# Nguyen_Ly.net
KiCad netlist of a schematic drawn in Altium Designer
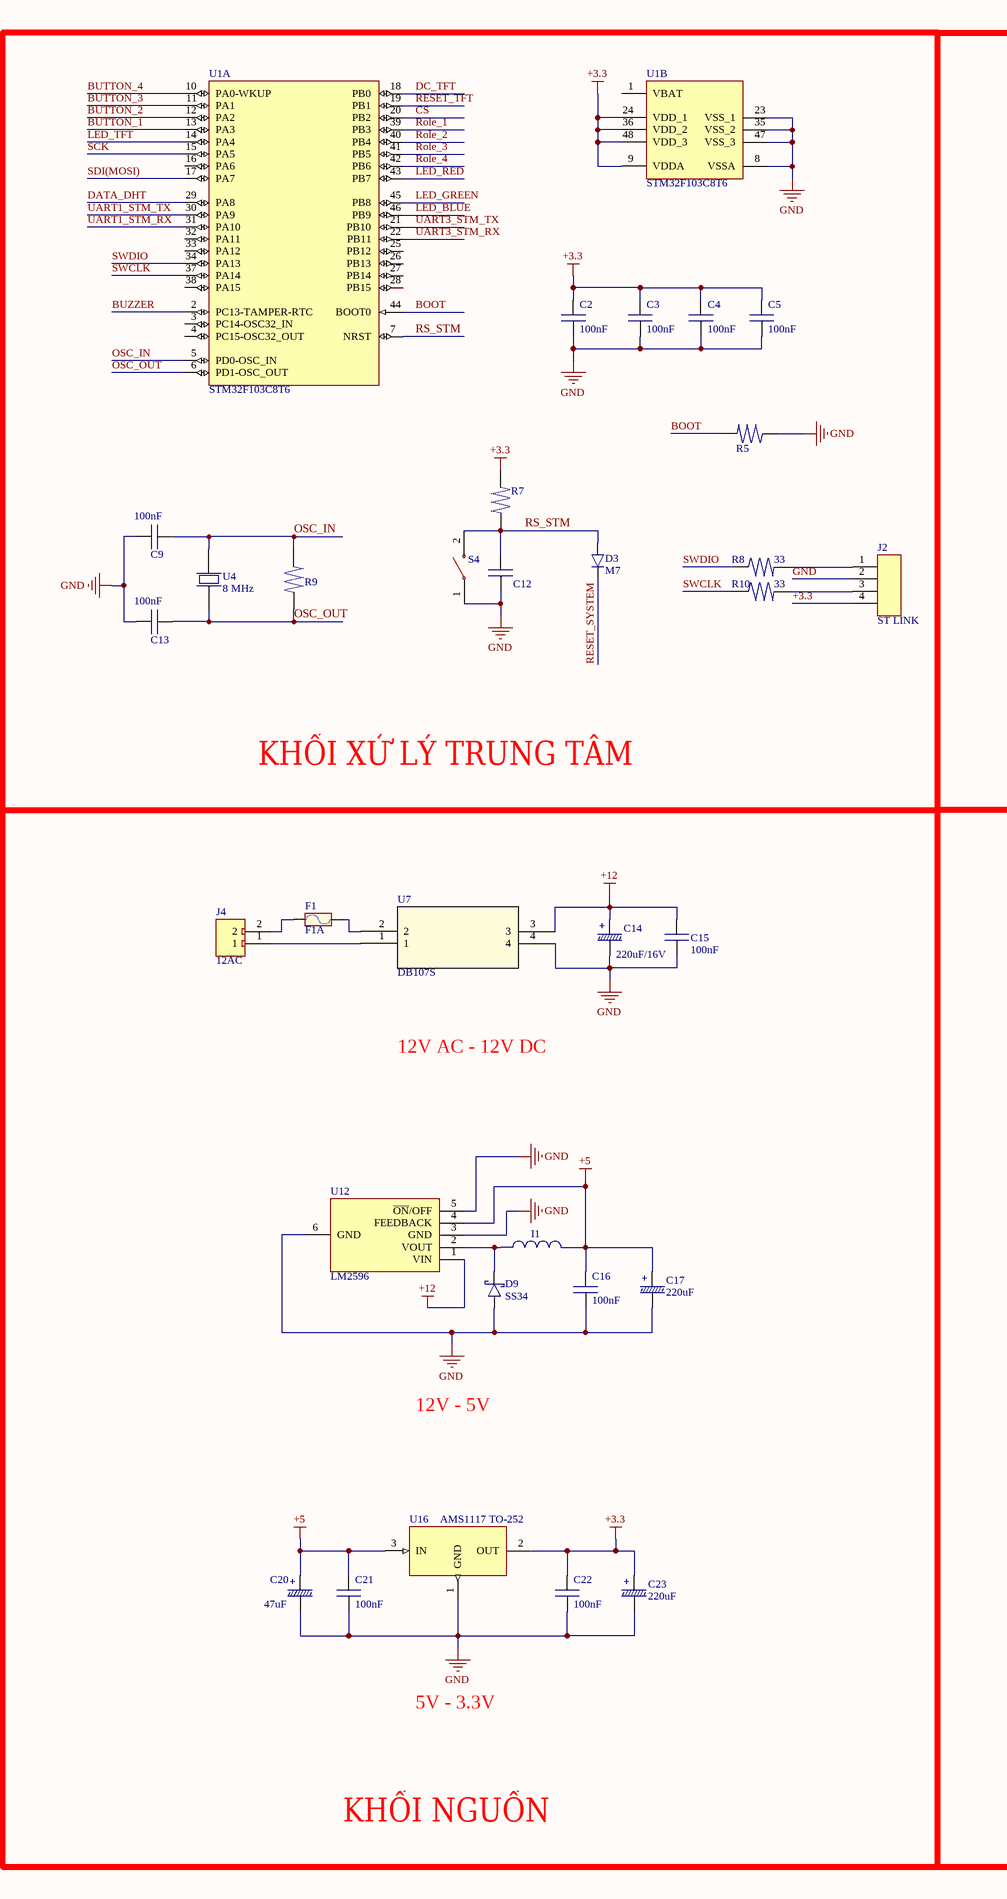
[diagram p0: Nguyen_Ly.SchDoc, left]
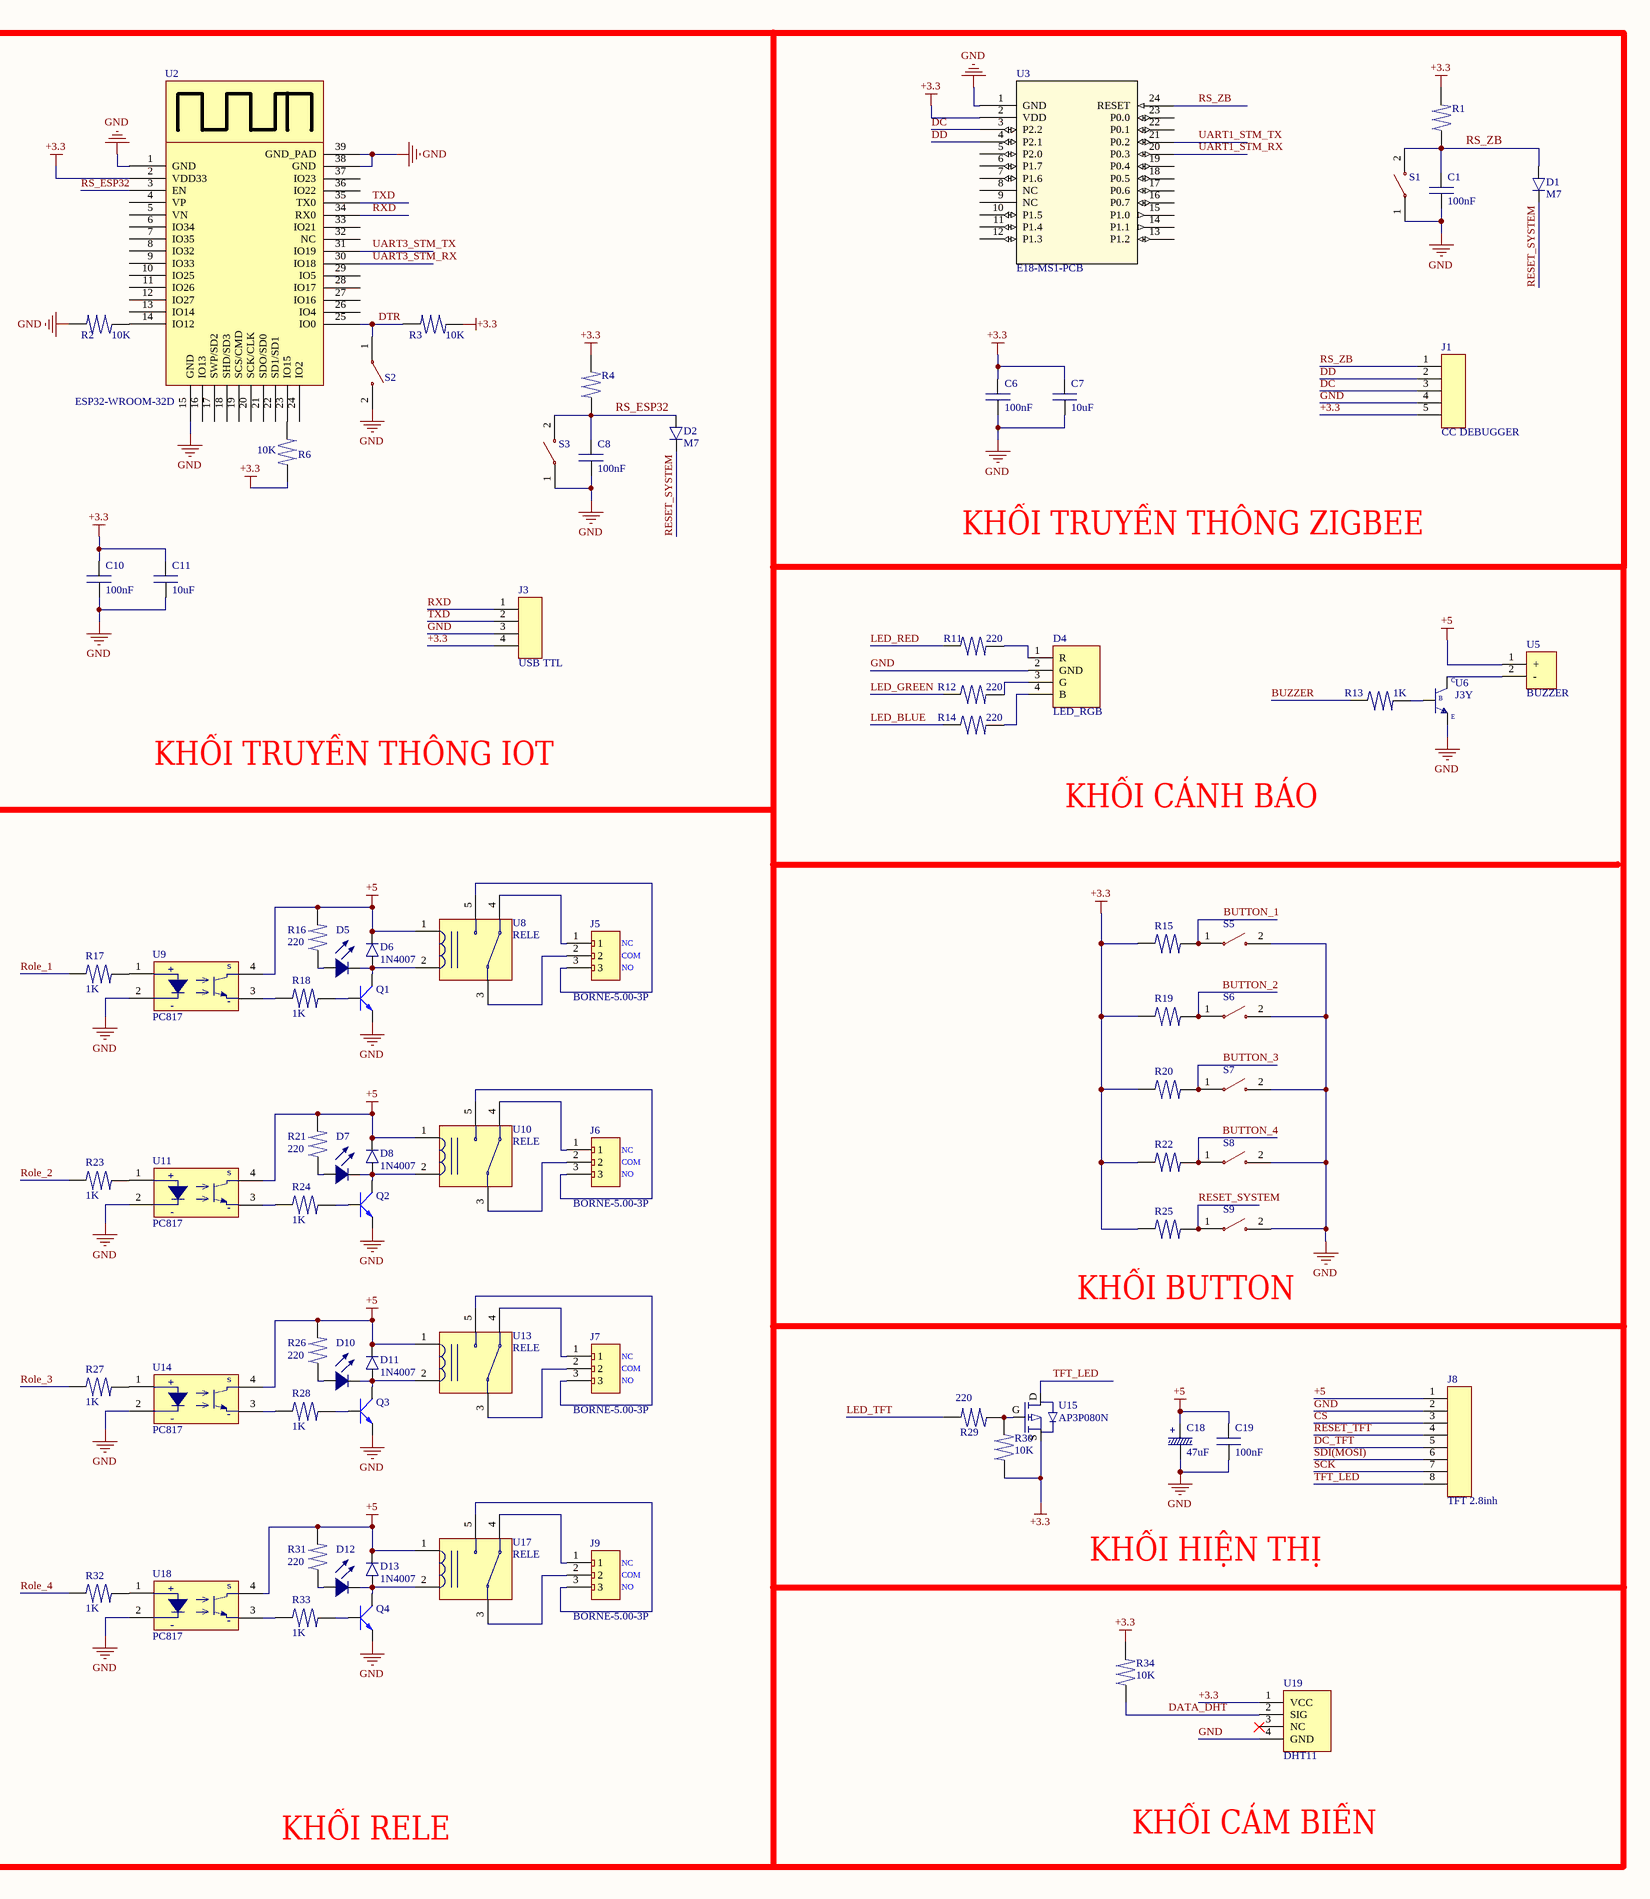
[diagram p1: Nguyen_Ly.SchDoc, right]

(export (version "E")
  (design (tool "Eeschema 10.0.6"))
  (components
    (comp (ref "C1")
      (value "100nF")
      (footprint "CAPACITOR 0805")
      (description "Generic Capacitor 0805, 2x1.25x1.4mm.")
      (libsource (lib "MyComponents") (part "CAPACITOR 0805"))
    )
    (comp (ref "C2")
      (value "100nF")
      (footprint "CAPACITOR 0805")
      (description "Generic Capacitor 0805, 2x1.25x1.4mm.")
      (libsource (lib "MyComponents") (part "CAPACITOR 0805"))
    )
    (comp (ref "C3")
      (value "100nF")
      (footprint "CAPACITOR 0805")
      (description "Generic Capacitor 0805, 2x1.25x1.4mm.")
      (libsource (lib "MyComponents") (part "CAPACITOR 0805"))
    )
    (comp (ref "C4")
      (value "100nF")
      (footprint "CAPACITOR 0805")
      (description "Generic Capacitor 0805, 2x1.25x1.4mm.")
      (libsource (lib "MyComponents") (part "CAPACITOR 0805"))
    )
    (comp (ref "C5")
      (value "100nF")
      (footprint "CAPACITOR 0805")
      (description "Generic Capacitor 0805, 2x1.25x1.4mm.")
      (libsource (lib "MyComponents") (part "CAPACITOR 0805"))
    )
    (comp (ref "C6")
      (value "100nF")
      (footprint "CAPACITOR 0805")
      (description "Generic Capacitor 0805, 2x1.25x1.4mm.")
      (libsource (lib "MyComponents") (part "CAPACITOR 0805"))
    )
    (comp (ref "C7")
      (value "10uF")
      (footprint "CAPACITOR 0805")
      (description "Generic Capacitor 0805, 2x1.25x1.4mm.")
      (libsource (lib "MyComponents") (part "CAPACITOR 0805"))
    )
    (comp (ref "C8")
      (value "100nF")
      (footprint "CAPACITOR 0805")
      (description "Generic Capacitor 0805, 2x1.25x1.4mm.")
      (libsource (lib "MyComponents") (part "CAPACITOR 0805"))
    )
    (comp (ref "C9")
      (value "100nF")
      (footprint "CAPACITOR 0805")
      (description "Generic Capacitor 0805, 2x1.25x1.4mm.")
      (libsource (lib "MyComponents") (part "CAPACITOR 0805"))
    )
    (comp (ref "C10")
      (value "100nF")
      (footprint "CAPACITOR 0805")
      (description "Generic Capacitor 0805, 2x1.25x1.4mm.")
      (libsource (lib "MyComponents") (part "CAPACITOR 0805"))
    )
    (comp (ref "C11")
      (value "10uF")
      (footprint "CAPACITOR 0805")
      (description "Generic Capacitor 0805, 2x1.25x1.4mm.")
      (libsource (lib "MyComponents") (part "CAPACITOR 0805"))
    )
    (comp (ref "C12")
      (value "CAPACITOR 0805")
      (footprint "CAPACITOR 0805")
      (description "Generic Capacitor 0805, 2x1.25x1.4mm.")
      (libsource (lib "MyComponents") (part "CAPACITOR 0805"))
    )
    (comp (ref "C13")
      (value "100nF")
      (footprint "CAPACITOR 0805")
      (description "Generic Capacitor 0805, 2x1.25x1.4mm.")
      (libsource (lib "MyComponents") (part "CAPACITOR 0805"))
    )
    (comp (ref "C14")
      (value "220uF/16V")
      (footprint "ALUMINUM_7mm")
      (description "Aluminum Capacitor 220uF/16V 7mm")
      (libsource (lib "MyComponents") (part "220uF/16V"))
    )
    (comp (ref "C15")
      (value "100nF")
      (footprint "CAPACITOR 0805")
      (description "Generic Capacitor 0805, 2x1.25x1.4mm.")
      (libsource (lib "MyComponents") (part "CAPACITOR 0805"))
    )
    (comp (ref "C16")
      (value "100nF")
      (footprint "CAPACITOR 0805")
      (description "Generic Capacitor 0805, 2x1.25x1.4mm.")
      (libsource (lib "MyComponents") (part "CAPACITOR 0805"))
    )
    (comp (ref "C17")
      (value "220uF")
      (footprint "ALUMINUM_7mm")
      (description "Aluminum Capacitor 220uF/16V 7mm")
      (libsource (lib "MyComponents") (part "220uF/16V"))
    )
    (comp (ref "C18")
      (value "47uF")
      (footprint "ALUMINUM_5mm")
      (description "Aluminum Capacitor 47uF/16V 5mm")
      (libsource (lib "MyComponents") (part "47uF/16V"))
    )
    (comp (ref "C19")
      (value "100nF")
      (footprint "CAPACITOR 0805")
      (description "Generic Capacitor 0805, 2x1.25x1.4mm.")
      (libsource (lib "MyComponents") (part "CAPACITOR 0805"))
    )
    (comp (ref "C20")
      (value "47uF")
      (footprint "ALUMINUM_5mm")
      (description "Aluminum Capacitor 47uF/16V 5mm")
      (libsource (lib "MyComponents") (part "47uF/16V"))
    )
    (comp (ref "C21")
      (value "100nF")
      (footprint "CAPACITOR 0805")
      (description "Generic Capacitor 0805, 2x1.25x1.4mm.")
      (libsource (lib "MyComponents") (part "CAPACITOR 0805"))
    )
    (comp (ref "C22")
      (value "100nF")
      (footprint "CAPACITOR 0805")
      (description "Generic Capacitor 0805, 2x1.25x1.4mm.")
      (libsource (lib "MyComponents") (part "CAPACITOR 0805"))
    )
    (comp (ref "C23")
      (value "220uF")
      (footprint "ALUMINUM_7mm")
      (description "Aluminum Capacitor 220uF/16V 7mm")
      (libsource (lib "MyComponents") (part "220uF/16V"))
    )
    (comp (ref "D1")
      (value "M7")
      (footprint "DIODE_SMA")
      (description "Rectifiers Diode 1000V 1A SMA")
      (libsource (lib "MyComponents") (part "M7"))
    )
    (comp (ref "D2")
      (value "M7")
      (footprint "DIODE_SMA")
      (description "Rectifiers Diode 1000V 1A SMA")
      (libsource (lib "MyComponents") (part "M7"))
    )
    (comp (ref "D3")
      (value "M7")
      (footprint "DIODE_SMA")
      (description "Rectifiers Diode 1000V 1A SMA")
      (libsource (lib "MyComponents") (part "M7"))
    )
    (comp (ref "D4")
      (value "LED_RGB")
      (footprint "LED_RGB_5mm")
      (description "LED RGB 4 Pins 5mm Common Cathode.")
      (libsource (lib "MyComponents") (part "LED_RGB_5mm"))
    )
    (comp (ref "D5")
      (value "LED_5mm_RED")
      (footprint "LED_5mm_RED")
      (description "LED PTH 5mm Red.")
      (libsource (lib "MyComponents") (part "LED_5mm_RED"))
    )
    (comp (ref "D6")
      (value "1N4007")
      (footprint "1N4007")
      (description "Rectifier Diode 1000V 1A DO-41")
      (libsource (lib "MyComponents") (part "1N4007"))
    )
    (comp (ref "D7")
      (value "LED_5mm_RED")
      (footprint "LED_5mm_RED")
      (description "LED PTH 5mm Red.")
      (libsource (lib "MyComponents") (part "LED_5mm_RED"))
    )
    (comp (ref "D8")
      (value "1N4007")
      (footprint "1N4007")
      (description "Rectifier Diode 1000V 1A DO-41")
      (libsource (lib "MyComponents") (part "1N4007"))
    )
    (comp (ref "D9")
      (value "SS34")
      (footprint "DIODE_SMA")
      (description "Rectifier Schottky 40V 3A SMA")
      (libsource (lib "MyComponents") (part "SS34"))
    )
    (comp (ref "D10")
      (value "LED_5mm_RED")
      (footprint "LED_5mm_RED")
      (description "LED PTH 5mm Red.")
      (libsource (lib "MyComponents") (part "LED_5mm_RED"))
    )
    (comp (ref "D11")
      (value "1N4007")
      (footprint "1N4007")
      (description "Rectifier Diode 1000V 1A DO-41")
      (libsource (lib "MyComponents") (part "1N4007"))
    )
    (comp (ref "D12")
      (value "LED_5mm_RED")
      (footprint "LED_5mm_RED")
      (description "LED PTH 5mm Red.")
      (libsource (lib "MyComponents") (part "LED_5mm_RED"))
    )
    (comp (ref "D13")
      (value "1N4007")
      (footprint "1N4007")
      (description "Rectifier Diode 1000V 1A DO-41")
      (libsource (lib "MyComponents") (part "1N4007"))
    )
    (comp (ref "F1")
      (value "F1A")
      (footprint "Fuse")
      (description "Fuse")
      (fields (field (name "DESIGNED BY") "VanDungEvn"))
      (libsource (lib "Thuvien3D") (part "Fuse"))
    )
    (comp (ref "I1")
      (value "1260")
      (footprint "1260")
      (description "Generic Encapsulated Inductor 1260.")
      (libsource (lib "MyComponents") (part "1260"))
    )
    (comp (ref "J1")
      (value "CC DEBUGGER")
      (footprint "MALE-2.54-5P")
      (description "Male Header Connector 2.54mm 5 Pins.")
      (libsource (lib "MyComponents") (part "MALE-2.54-5P"))
    )
    (comp (ref "J2")
      (value "ST LINK")
      (footprint "MALE-2.54-4P")
      (description "Male Header Connector 2.54mm 4 Pins.")
      (libsource (lib "MyComponents") (part "MALE-2.54-4P"))
    )
    (comp (ref "J3")
      (value "USB TTL")
      (footprint "MALE-2.54-4P")
      (description "Male Header Connector 2.54mm 4 Pins.")
      (libsource (lib "MyComponents") (part "MALE-2.54-4P"))
    )
    (comp (ref "J4")
      (value "12AC")
      (footprint "BORNE-5.00-2P")
      (description "Borne 2 Vias, Pitch 5mm.")
      (libsource (lib "MyComponents") (part "BORNE-5.00-2P"))
    )
    (comp (ref "J5")
      (value "BORNE-5.00-3P")
      (footprint "BORNE-5.00-3P")
      (description "Borne 3 Vias, Pitch 5mm.")
      (libsource (lib "MyComponents") (part "BORNE-5.00-3P"))
    )
    (comp (ref "J6")
      (value "BORNE-5.00-3P")
      (footprint "BORNE-5.00-3P")
      (description "Borne 3 Vias, Pitch 5mm.")
      (libsource (lib "MyComponents") (part "BORNE-5.00-3P"))
    )
    (comp (ref "J7")
      (value "BORNE-5.00-3P")
      (footprint "BORNE-5.00-3P")
      (description "Borne 3 Vias, Pitch 5mm.")
      (libsource (lib "MyComponents") (part "BORNE-5.00-3P"))
    )
    (comp (ref "J8")
      (value "TFT 2.8inh")
      (footprint "MALE-2.54-8P")
      (description "Male Header Connector 2.54mm 8 Pins.")
      (libsource (lib "MyComponents") (part "MALE-2.54-8P"))
    )
    (comp (ref "J9")
      (value "BORNE-5.00-3P")
      (footprint "BORNE-5.00-3P")
      (description "Borne 3 Vias, Pitch 5mm.")
      (libsource (lib "MyComponents") (part "BORNE-5.00-3P"))
    )
    (comp (ref "Q1")
      (value "C9014")
      (footprint "QTO-92")
      (description "P 600mW, EBC")
      (libsource (lib "Thuvien3D") (part "NPN_EBC"))
    )
    (comp (ref "Q2")
      (value "C9014")
      (footprint "QTO-92")
      (description "P 600mW, EBC")
      (libsource (lib "Thuvien3D") (part "NPN_EBC"))
    )
    (comp (ref "Q3")
      (value "C9014")
      (footprint "QTO-92")
      (description "P 600mW, EBC")
      (libsource (lib "Thuvien3D") (part "NPN_EBC"))
    )
    (comp (ref "Q4")
      (value "C9014")
      (footprint "QTO-92")
      (description "P 600mW, EBC")
      (libsource (lib "Thuvien3D") (part "NPN_EBC"))
    )
    (comp (ref "R1")
      (value "RESISTOR_0805")
      (footprint "RESISTOR_0805")
      (description "Generic Resistor 0805.")
      (libsource (lib "MyComponents") (part "RESISTOR_0805"))
    )
    (comp (ref "R2")
      (value "10K")
      (footprint "RESISTOR_0805")
      (description "Generic Resistor 0805.")
      (libsource (lib "MyComponents") (part "RESISTOR_0805"))
    )
    (comp (ref "R3")
      (value "10K")
      (footprint "RESISTOR_0805")
      (description "Generic Resistor 0805.")
      (libsource (lib "MyComponents") (part "RESISTOR_0805"))
    )
    (comp (ref "R4")
      (value "RESISTOR_0805")
      (footprint "RESISTOR_0805")
      (description "Generic Resistor 0805.")
      (libsource (lib "MyComponents") (part "RESISTOR_0805"))
    )
    (comp (ref "R5")
      (value "RESISTOR_0805")
      (footprint "RESISTOR_0805")
      (description "Generic Resistor 0805.")
      (libsource (lib "MyComponents") (part "RESISTOR_0805"))
    )
    (comp (ref "R6")
      (value "10K")
      (footprint "RESISTOR_0805")
      (description "Generic Resistor 0805.")
      (libsource (lib "MyComponents") (part "RESISTOR_0805"))
    )
    (comp (ref "R7")
      (value "RESISTOR_0805")
      (footprint "RESISTOR_0805")
      (description "Generic Resistor 0805.")
      (libsource (lib "MyComponents") (part "RESISTOR_0805"))
    )
    (comp (ref "R8")
      (value "33")
      (footprint "RESISTOR_0805")
      (description "Generic Resistor 0805.")
      (libsource (lib "MyComponents") (part "RESISTOR_0805"))
    )
    (comp (ref "R9")
      (value "RESISTOR_0805")
      (footprint "RESISTOR_0805")
      (description "Generic Resistor 0805.")
      (libsource (lib "MyComponents") (part "RESISTOR_0805"))
    )
    (comp (ref "R10")
      (value "33")
      (footprint "RESISTOR_0805")
      (description "Generic Resistor 0805.")
      (libsource (lib "MyComponents") (part "RESISTOR_0805"))
    )
    (comp (ref "R11")
      (value "220")
      (footprint "RESISTOR_0805")
      (description "Generic Resistor 0805.")
      (libsource (lib "MyComponents") (part "RESISTOR_0805"))
    )
    (comp (ref "R12")
      (value "220")
      (footprint "RESISTOR_0805")
      (description "Generic Resistor 0805.")
      (libsource (lib "MyComponents") (part "RESISTOR_0805"))
    )
    (comp (ref "R13")
      (value "1K")
      (footprint "RESISTOR_0805")
      (description "Generic Resistor 0805.")
      (libsource (lib "MyComponents") (part "RESISTOR_0805"))
    )
    (comp (ref "R14")
      (value "220")
      (footprint "RESISTOR_0805")
      (description "Generic Resistor 0805.")
      (libsource (lib "MyComponents") (part "RESISTOR_0805"))
    )
    (comp (ref "R15")
      (value "RESISTOR_0805")
      (footprint "RESISTOR_0805")
      (description "Generic Resistor 0805.")
      (libsource (lib "MyComponents") (part "RESISTOR_0805"))
    )
    (comp (ref "R16")
      (value "220")
      (footprint "RESISTOR_PTH_9.5mm")
      (description "Generic Resistor 9.5mm.")
      (libsource (lib "MyComponents") (part "RESISTOR_9.5mm"))
    )
    (comp (ref "R17")
      (value "1K")
      (footprint "RESISTOR_PTH_9.5mm")
      (description "Generic Resistor 9.5mm.")
      (libsource (lib "MyComponents") (part "RESISTOR_9.5mm"))
    )
    (comp (ref "R18")
      (value "1K")
      (footprint "RESISTOR_PTH_9.5mm")
      (description "Generic Resistor 9.5mm.")
      (libsource (lib "MyComponents") (part "RESISTOR_9.5mm"))
    )
    (comp (ref "R19")
      (value "RESISTOR_0805")
      (footprint "RESISTOR_0805")
      (description "Generic Resistor 0805.")
      (libsource (lib "MyComponents") (part "RESISTOR_0805"))
    )
    (comp (ref "R20")
      (value "RESISTOR_0805")
      (footprint "RESISTOR_0805")
      (description "Generic Resistor 0805.")
      (libsource (lib "MyComponents") (part "RESISTOR_0805"))
    )
    (comp (ref "R21")
      (value "220")
      (footprint "RESISTOR_PTH_9.5mm")
      (description "Generic Resistor 9.5mm.")
      (libsource (lib "MyComponents") (part "RESISTOR_9.5mm"))
    )
    (comp (ref "R22")
      (value "RESISTOR_0805")
      (footprint "RESISTOR_0805")
      (description "Generic Resistor 0805.")
      (libsource (lib "MyComponents") (part "RESISTOR_0805"))
    )
    (comp (ref "R23")
      (value "1K")
      (footprint "RESISTOR_PTH_9.5mm")
      (description "Generic Resistor 9.5mm.")
      (libsource (lib "MyComponents") (part "RESISTOR_9.5mm"))
    )
    (comp (ref "R24")
      (value "1K")
      (footprint "RESISTOR_PTH_9.5mm")
      (description "Generic Resistor 9.5mm.")
      (libsource (lib "MyComponents") (part "RESISTOR_9.5mm"))
    )
    (comp (ref "R25")
      (value "RESISTOR_0805")
      (footprint "RESISTOR_0805")
      (description "Generic Resistor 0805.")
      (libsource (lib "MyComponents") (part "RESISTOR_0805"))
    )
    (comp (ref "R26")
      (value "220")
      (footprint "RESISTOR_PTH_9.5mm")
      (description "Generic Resistor 9.5mm.")
      (libsource (lib "MyComponents") (part "RESISTOR_9.5mm"))
    )
    (comp (ref "R27")
      (value "1K")
      (footprint "RESISTOR_PTH_9.5mm")
      (description "Generic Resistor 9.5mm.")
      (libsource (lib "MyComponents") (part "RESISTOR_9.5mm"))
    )
    (comp (ref "R28")
      (value "1K")
      (footprint "RESISTOR_PTH_9.5mm")
      (description "Generic Resistor 9.5mm.")
      (libsource (lib "MyComponents") (part "RESISTOR_9.5mm"))
    )
    (comp (ref "R29")
      (value "220")
      (footprint "RESISTOR_0805")
      (description "Generic Resistor 0805.")
      (libsource (lib "MyComponents") (part "RESISTOR_0805"))
    )
    (comp (ref "R30")
      (value "10K")
      (footprint "RESISTOR_0805")
      (description "Generic Resistor 0805.")
      (libsource (lib "MyComponents") (part "RESISTOR_0805"))
    )
    (comp (ref "R31")
      (value "220")
      (footprint "RESISTOR_PTH_9.5mm")
      (description "Generic Resistor 9.5mm.")
      (libsource (lib "MyComponents") (part "RESISTOR_9.5mm"))
    )
    (comp (ref "R32")
      (value "1K")
      (footprint "RESISTOR_PTH_9.5mm")
      (description "Generic Resistor 9.5mm.")
      (libsource (lib "MyComponents") (part "RESISTOR_9.5mm"))
    )
    (comp (ref "R33")
      (value "1K")
      (footprint "RESISTOR_PTH_9.5mm")
      (description "Generic Resistor 9.5mm.")
      (libsource (lib "MyComponents") (part "RESISTOR_9.5mm"))
    )
    (comp (ref "R34")
      (value "10K")
      (footprint "RESISTOR_0805")
      (description "Generic Resistor 0805.")
      (libsource (lib "MyComponents") (part "RESISTOR_0805"))
    )
    (comp (ref "S1")
      (value "PUSH_BUTTON_SMD_3X4X2")
      (footprint "PUSH_BUTTON_SMD_3X4X2")
      (description "Push Button Tactile Switch SMD 2 Pins 3x4x2mm.")
      (libsource (lib "MyComponents") (part "PUSH_BUTTON_SMD_3X4X2"))
    )
    (comp (ref "S2")
      (value "PUSH_BUTTON_SMD_3X4X2")
      (footprint "PUSH_BUTTON_SMD_3X4X2")
      (description "Push Button Tactile Switch SMD 2 Pins 3x4x2mm.")
      (libsource (lib "MyComponents") (part "PUSH_BUTTON_SMD_3X4X2"))
    )
    (comp (ref "S3")
      (value "PUSH_BUTTON_SMD_3X4X2")
      (footprint "PUSH_BUTTON_SMD_3X4X2")
      (description "Push Button Tactile Switch SMD 2 Pins 3x4x2mm.")
      (libsource (lib "MyComponents") (part "PUSH_BUTTON_SMD_3X4X2"))
    )
    (comp (ref "S4")
      (value "PUSH_BUTTON_SMD_3X4X2")
      (footprint "PUSH_BUTTON_SMD_3X4X2")
      (description "Push Button Tactile Switch SMD 2 Pins 3x4x2mm.")
      (libsource (lib "MyComponents") (part "PUSH_BUTTON_SMD_3X4X2"))
    )
    (comp (ref "S5")
      (value "PUSH_BUTTON_12X12")
      (footprint "PUSH_BUTTON_12X12_BLUE")
      (description "Push Button Tactile Switch PTH 4 Pins 12x12mm.")
      (libsource (lib "MyComponents") (part "PUSH_BUTTON_12X12"))
    )
    (comp (ref "S6")
      (value "PUSH_BUTTON_12X12")
      (footprint "PUSH_BUTTON_12X12_GREEN")
      (description "Push Button Tactile Switch PTH 4 Pins 12x12mm.")
      (libsource (lib "MyComponents") (part "PUSH_BUTTON_12X12"))
    )
    (comp (ref "S7")
      (value "PUSH_BUTTON_12X12")
      (footprint "PUSH_BUTTON_12X12_RED")
      (description "Push Button Tactile Switch PTH 4 Pins 12x12mm.")
      (libsource (lib "MyComponents") (part "PUSH_BUTTON_12X12"))
    )
    (comp (ref "S8")
      (value "PUSH_BUTTON_12X12")
      (footprint "PUSH_BUTTON_12X12_YELLOW")
      (description "Push Button Tactile Switch PTH 4 Pins 12x12mm.")
      (libsource (lib "MyComponents") (part "PUSH_BUTTON_12X12"))
    )
    (comp (ref "S9")
      (value "PUSH_BUTTON_6X6")
      (footprint "PUSH_BUTTON_6X6")
      (description "Push Button Tactile Switch PTH 4 Pins 6x6mm.")
      (libsource (lib "MyComponents") (part "PUSH_BUTTON_6X6"))
    )
    (comp (ref "U1")
      (value "STM32F103C8T6")
      (footprint "STM-LQFP48_N")
      (libsource (lib "STMicroelectronics STM32 F1") (part "STM32F103C8T6"))
    )
    (comp (ref "U2")
      (value "ESP32-WROOM-32D")
      (footprint "ESP32-WROOM-32D")
      (description "Chip SMD 39 Pads Wifi 2.4GHz BLE 4.2 18x25.5mm w/ Antenna.")
      (libsource (lib "MyComponents") (part "ESP32-WROOM-32D"))
    )
    (comp (ref "U3")
      (value "E18-MS1-PCB")
      (footprint "E18-MS1-PCB_BYT")
      (description "No Description Available")
      (fields (field (name "COPYRIGHT") "Copyright (C) 2026 Ultra Librarian. All rights reserved."))
      (libsource (lib "Integrated_Library1") (part "E18-MS1-PCB"))
    )
    (comp (ref "U4")
      (value "8 MHz")
      (footprint "CRISTAL_16Mhz")
      (description "CRYSTAL 16MHZ, PTH and SMD")
      (libsource (lib "MyComponents") (part "CRISTAL_16Mhz"))
    )
    (comp (ref "U5")
      (value "BUZZER")
      (footprint "BUZZER_12mm")
      (description "BUZZER MAGNETIC 12MM")
      (libsource (lib "MyComponents") (part "BUZZER_12mm"))
    )
    (comp (ref "U6")
      (value "J3Y")
      (footprint "J3Y")
      (description "TRANSISTOR BIPOLAR (BJT) NPN 25V 500mA SOT-23-3")
      (libsource (lib "MyComponents") (part "J3Y"))
    )
    (comp (ref "U7")
      (value "DB107S")
      (footprint "SOIC_B107S_RTN")
      (description "Description")
      (fields (field (name "COPYRIGHT") "Copyright (C) 2025 Ultra Librarian. All rights reserved."))
      (libsource (lib "DB107S") (part "DB107S"))
    )
    (comp (ref "U8")
      (value "RELE")
      (footprint "RELE")
      (description "Generic Rele PTH 5 Pins.")
      (libsource (lib "MyComponents") (part "RELE"))
    )
    (comp (ref "U9")
      (value "PC817")
      (footprint "PC817_DIP")
      (description "Optocouplers Phototransistor 4 Pins, DIP and SMD.")
      (libsource (lib "MyComponents") (part "PC817"))
    )
    (comp (ref "U10")
      (value "RELE")
      (footprint "RELE")
      (description "Generic Rele PTH 5 Pins.")
      (libsource (lib "MyComponents") (part "RELE"))
    )
    (comp (ref "U11")
      (value "PC817")
      (footprint "PC817_DIP")
      (description "Optocouplers Phototransistor 4 Pins, DIP and SMD.")
      (libsource (lib "MyComponents") (part "PC817"))
    )
    (comp (ref "U12")
      (value "LM2596")
      (footprint "LM2596")
      (description "IC BUCK STEP DOWN 3A TO-263-6")
      (libsource (lib "MyComponents") (part "LM2596"))
    )
    (comp (ref "U13")
      (value "RELE")
      (footprint "RELE")
      (description "Generic Rele PTH 5 Pins.")
      (libsource (lib "MyComponents") (part "RELE"))
    )
    (comp (ref "U14")
      (value "PC817")
      (footprint "PC817_DIP")
      (description "Optocouplers Phototransistor 4 Pins, DIP and SMD.")
      (libsource (lib "MyComponents") (part "PC817"))
    )
    (comp (ref "U15")
      (value "AP3P080N")
      (footprint "SOT23-3")
      (description "Mosfet PNP")
      (libsource (lib "MyComponents") (part "AP3P080N"))
    )
    (comp (ref "U16")
      (value "AMS1117 TO-252")
      (footprint "DPAK457P1010X238-3N")
      (description "Linear Voltage Regulator IC Positive Fixed 1 Output 1A TO-252-3")
      (fields (field (name "MP") "AZ1117D-3.3TRE1") (field (name "MF") "Diodes Inc."))
      (libsource (lib "AZ1117D-3.3TRE1") (part "AZ1117D-3.3TRE1"))
    )
    (comp (ref "U17")
      (value "RELE")
      (footprint "RELE")
      (description "Generic Rele PTH 5 Pins.")
      (libsource (lib "MyComponents") (part "RELE"))
    )
    (comp (ref "U18")
      (value "PC817")
      (footprint "PC817_DIP")
      (description "Optocouplers Phototransistor 4 Pins, DIP and SMD.")
      (libsource (lib "MyComponents") (part "PC817"))
    )
    (comp (ref "U19")
      (value "DHT11")
      (footprint "DHT11")
      (description "SENSOR HUMIDITY/TEMPERATURE")
      (libsource (lib "MyComponents") (part "DHT11"))
    )
  )
  (nets
    (net (code "1") (name "+3.3") (class "Default")
      (node (ref "C10") (pin "2") (pinfunction "2_2") (pintype "passive"))
      (node (ref "C11") (pin "2") (pinfunction "2_2") (pintype "passive"))
      (node (ref "C2") (pin "2") (pinfunction "2_2") (pintype "passive"))
      (node (ref "C22") (pin "2") (pinfunction "2_2") (pintype "passive"))
      (node (ref "C23") (pin "1") (pinfunction "1_1") (pintype "passive"))
      (node (ref "C3") (pin "2") (pinfunction "2_2") (pintype "passive"))
      (node (ref "C4") (pin "2") (pinfunction "2_2") (pintype "passive"))
      (node (ref "C5") (pin "2") (pinfunction "2_2") (pintype "passive"))
      (node (ref "C6") (pin "2") (pinfunction "2_2") (pintype "passive"))
      (node (ref "C7") (pin "2") (pinfunction "2_2") (pintype "passive"))
      (node (ref "J1") (pin "5") (pintype "passive"))
      (node (ref "J2") (pin "4") (pintype "passive"))
      (node (ref "J3") (pin "4") (pintype "passive"))
      (node (ref "R1") (pin "2") (pinfunction "2_2") (pintype "passive"))
      (node (ref "R15") (pin "1") (pinfunction "1_1") (pintype "passive"))
      (node (ref "R19") (pin "1") (pinfunction "1_1") (pintype "passive"))
      (node (ref "R20") (pin "1") (pinfunction "1_1") (pintype "passive"))
      (node (ref "R22") (pin "1") (pinfunction "1_1") (pintype "passive"))
      (node (ref "R25") (pin "1") (pinfunction "1_1") (pintype "passive"))
      (node (ref "R3") (pin "1") (pinfunction "1_1") (pintype "passive"))
      (node (ref "R30") (pin "1") (pinfunction "1_1") (pintype "passive"))
      (node (ref "R34") (pin "2") (pinfunction "2_2") (pintype "passive"))
      (node (ref "R4") (pin "2") (pinfunction "2_2") (pintype "passive"))
      (node (ref "R6") (pin "2") (pinfunction "2_2") (pintype "passive"))
      (node (ref "R7") (pin "2") (pinfunction "2_2") (pintype "passive"))
      (node (ref "U1") (pin "24") (pinfunction "VDD_1_24") (pintype "power_in"))
      (node (ref "U1") (pin "36") (pinfunction "VDD_2_36") (pintype "power_in"))
      (node (ref "U1") (pin "48") (pinfunction "VDD_3_48") (pintype "power_in"))
      (node (ref "U1") (pin "9") (pinfunction "VDDA_9") (pintype "power_in"))
      (node (ref "U15") (pin "S") (pinfunction "S_S") (pintype "passive"))
      (node (ref "U16") (pin "2") (pinfunction "OUT_2") (pintype "power_in"))
      (node (ref "U19") (pin "1") (pinfunction "VCC_1") (pintype "passive"))
      (node (ref "U2") (pin "2") (pinfunction "VDD33_2") (pintype "passive"))
      (node (ref "U3") (pin "2") (pinfunction "VDD_2") (pintype "power_in"))
    )
    (net (code "2") (name "+5") (class "Default")
      (node (ref "C16") (pin "2") (pinfunction "2_2") (pintype "passive"))
      (node (ref "C17") (pin "1") (pinfunction "1_1") (pintype "passive"))
      (node (ref "C18") (pin "1") (pinfunction "1_1") (pintype "passive"))
      (node (ref "C19") (pin "2") (pinfunction "2_2") (pintype "passive"))
      (node (ref "C20") (pin "1") (pinfunction "1_1") (pintype "passive"))
      (node (ref "C21") (pin "2") (pinfunction "2_2") (pintype "passive"))
      (node (ref "D11") (pin "2") (pintype "passive"))
      (node (ref "D13") (pin "2") (pintype "passive"))
      (node (ref "D6") (pin "2") (pintype "passive"))
      (node (ref "D8") (pin "2") (pintype "passive"))
      (node (ref "I1") (pin "2") (pinfunction "2_2") (pintype "passive"))
      (node (ref "J8") (pin "1") (pintype "passive"))
      (node (ref "R16") (pin "2") (pinfunction "2_2") (pintype "passive"))
      (node (ref "R21") (pin "2") (pinfunction "2_2") (pintype "passive"))
      (node (ref "R26") (pin "2") (pinfunction "2_2") (pintype "passive"))
      (node (ref "R31") (pin "2") (pinfunction "2_2") (pintype "passive"))
      (node (ref "U10") (pin "1") (pintype "passive"))
      (node (ref "U11") (pin "4") (pinfunction "SIGNAL_4") (pintype "passive"))
      (node (ref "U12") (pin "4") (pinfunction "FEEDBACK_4") (pintype "passive"))
      (node (ref "U13") (pin "1") (pintype "passive"))
      (node (ref "U14") (pin "4") (pinfunction "SIGNAL_4") (pintype "passive"))
      (node (ref "U16") (pin "3") (pinfunction "IN_3") (pintype "input"))
      (node (ref "U17") (pin "1") (pintype "passive"))
      (node (ref "U18") (pin "4") (pinfunction "SIGNAL_4") (pintype "passive"))
      (node (ref "U5") (pin "1") (pinfunction "+_1") (pintype "passive"))
      (node (ref "U8") (pin "1") (pintype "passive"))
      (node (ref "U9") (pin "4") (pinfunction "SIGNAL_4") (pintype "passive"))
    )
    (net (code "3") (name "+12") (class "Default")
      (node (ref "C14") (pin "1") (pinfunction "1_1") (pintype "passive"))
      (node (ref "C15") (pin "2") (pinfunction "2_2") (pintype "passive"))
      (node (ref "U12") (pin "1") (pinfunction "VIN_1") (pintype "passive"))
      (node (ref "U7") (pin "3") (pinfunction "3_3") (pintype "passive"))
    )
    (net (code "4") (name "/BOOT") (class "Default")
      (node (ref "R5") (pin "2") (pinfunction "2_2") (pintype "passive"))
      (node (ref "U1") (pin "44") (pinfunction "BOOT0_44") (pintype "input"))
    )
    (net (code "5") (name "/BUTTON_1") (class "Default")
      (node (ref "R15") (pin "2") (pinfunction "2_2") (pintype "passive"))
      (node (ref "S5") (pin "1") (pinfunction "1_1") (pintype "passive"))
      (node (ref "U1") (pin "13") (pinfunction "PA3_13") (pintype "bidirectional"))
    )
    (net (code "6") (name "/BUTTON_2") (class "Default")
      (node (ref "R19") (pin "2") (pinfunction "2_2") (pintype "passive"))
      (node (ref "S6") (pin "1") (pinfunction "1_1") (pintype "passive"))
      (node (ref "U1") (pin "12") (pinfunction "PA2_12") (pintype "bidirectional"))
    )
    (net (code "7") (name "/BUTTON_3") (class "Default")
      (node (ref "R20") (pin "2") (pinfunction "2_2") (pintype "passive"))
      (node (ref "S7") (pin "1") (pinfunction "1_1") (pintype "passive"))
      (node (ref "U1") (pin "11") (pinfunction "PA1_11") (pintype "bidirectional"))
    )
    (net (code "8") (name "/BUTTON_4") (class "Default")
      (node (ref "R22") (pin "2") (pinfunction "2_2") (pintype "passive"))
      (node (ref "S8") (pin "1") (pinfunction "1_1") (pintype "passive"))
      (node (ref "U1") (pin "10") (pinfunction "PA0-WKUP_10") (pintype "bidirectional"))
    )
    (net (code "9") (name "/BUZZER") (class "Default")
      (node (ref "R13") (pin "1") (pinfunction "1_1") (pintype "passive"))
      (node (ref "U1") (pin "2") (pinfunction "PC13-TAMPER-RTC_2") (pintype "bidirectional"))
    )
    (net (code "10") (name "/CS") (class "Default")
      (node (ref "J8") (pin "3") (pintype "passive"))
      (node (ref "U1") (pin "20") (pinfunction "PB2_20") (pintype "bidirectional"))
    )
    (net (code "11") (name "/DATA_DHT") (class "Default")
      (node (ref "R34") (pin "1") (pinfunction "1_1") (pintype "passive"))
      (node (ref "U1") (pin "29") (pinfunction "PA8_29") (pintype "bidirectional"))
      (node (ref "U19") (pin "2") (pinfunction "SIG_2") (pintype "passive"))
    )
    (net (code "12") (name "/DC") (class "Default")
      (node (ref "J1") (pin "3") (pintype "passive"))
      (node (ref "U3") (pin "3") (pinfunction "P2.2_3") (pintype "bidirectional"))
    )
    (net (code "13") (name "/DC_TFT") (class "Default")
      (node (ref "J8") (pin "5") (pintype "passive"))
      (node (ref "U1") (pin "18") (pinfunction "PB0_18") (pintype "bidirectional"))
    )
    (net (code "14") (name "/DD") (class "Default")
      (node (ref "J1") (pin "2") (pintype "passive"))
      (node (ref "U3") (pin "4") (pinfunction "P2.1_4") (pintype "bidirectional"))
    )
    (net (code "15") (name "/DTR") (class "Default")
      (node (ref "R3") (pin "2") (pinfunction "2_2") (pintype "passive"))
      (node (ref "S2") (pin "1") (pinfunction "1_1") (pintype "passive"))
      (node (ref "U2") (pin "25") (pinfunction "IO0_25") (pintype "passive"))
    )
    (net (code "16") (name "/LED_BLUE") (class "Default")
      (node (ref "R14") (pin "1") (pinfunction "1_1") (pintype "passive"))
      (node (ref "U1") (pin "46") (pinfunction "PB9_46") (pintype "bidirectional"))
    )
    (net (code "17") (name "/LED_GREEN") (class "Default")
      (node (ref "R12") (pin "1") (pinfunction "1_1") (pintype "passive"))
      (node (ref "U1") (pin "45") (pinfunction "PB8_45") (pintype "bidirectional"))
    )
    (net (code "18") (name "/LED_RED") (class "Default")
      (node (ref "R11") (pin "1") (pinfunction "1_1") (pintype "passive"))
      (node (ref "U1") (pin "43") (pinfunction "PB7_43") (pintype "bidirectional"))
    )
    (net (code "19") (name "/LED_TFT") (class "Default")
      (node (ref "R29") (pin "2") (pinfunction "2_2") (pintype "passive"))
      (node (ref "U1") (pin "14") (pinfunction "PA4_14") (pintype "bidirectional"))
    )
    (net (code "20") (name "/OSC_IN") (class "Default")
      (node (ref "C9") (pin "1") (pinfunction "1_1") (pintype "passive"))
      (node (ref "R9") (pin "1") (pinfunction "1_1") (pintype "passive"))
      (node (ref "U1") (pin "5") (pinfunction "PD0-OSC_IN_5") (pintype "bidirectional"))
      (node (ref "U4") (pin "2") (pinfunction "2_2") (pintype "power_in"))
    )
    (net (code "21") (name "/OSC_OUT") (class "Default")
      (node (ref "C13") (pin "1") (pinfunction "1_1") (pintype "passive"))
      (node (ref "R9") (pin "2") (pinfunction "2_2") (pintype "passive"))
      (node (ref "U1") (pin "6") (pinfunction "PD1-OSC_OUT_6") (pintype "bidirectional"))
      (node (ref "U4") (pin "1") (pinfunction "1_1") (pintype "power_in"))
    )
    (net (code "22") (name "/RESET_SYSTEM") (class "Default")
      (node (ref "D1") (pin "2") (pintype "passive"))
      (node (ref "D2") (pin "2") (pintype "passive"))
      (node (ref "D3") (pin "2") (pintype "passive"))
      (node (ref "R25") (pin "2") (pinfunction "2_2") (pintype "passive"))
      (node (ref "S9") (pin "1") (pinfunction "1_1") (pintype "passive"))
    )
    (net (code "23") (name "/RESET_TFT") (class "Default")
      (node (ref "J8") (pin "4") (pintype "passive"))
      (node (ref "U1") (pin "19") (pinfunction "PB1_19") (pintype "bidirectional"))
    )
    (net (code "24") (name "/RS_ESP32") (class "Default")
      (node (ref "C8") (pin "2") (pinfunction "2_2") (pintype "passive"))
      (node (ref "D2") (pin "1") (pinfunction "1_1") (pintype "passive"))
      (node (ref "R4") (pin "1") (pinfunction "1_1") (pintype "passive"))
      (node (ref "S3") (pin "2") (pinfunction "2_2") (pintype "passive"))
      (node (ref "U2") (pin "3") (pinfunction "EN_3") (pintype "passive"))
    )
    (net (code "25") (name "/RS_STM") (class "Default")
      (node (ref "C12") (pin "2") (pinfunction "2_2") (pintype "passive"))
      (node (ref "D3") (pin "1") (pinfunction "1_1") (pintype "passive"))
      (node (ref "R7") (pin "1") (pinfunction "1_1") (pintype "passive"))
      (node (ref "S4") (pin "2") (pinfunction "2_2") (pintype "passive"))
      (node (ref "U1") (pin "7") (pinfunction "NRST_7") (pintype "bidirectional"))
    )
    (net (code "26") (name "/RS_ZB") (class "Default")
      (node (ref "C1") (pin "2") (pinfunction "2_2") (pintype "passive"))
      (node (ref "D1") (pin "1") (pinfunction "1_1") (pintype "passive"))
      (node (ref "J1") (pin "1") (pintype "passive"))
      (node (ref "R1") (pin "1") (pinfunction "1_1") (pintype "passive"))
      (node (ref "S1") (pin "2") (pinfunction "2_2") (pintype "passive"))
      (node (ref "U3") (pin "24") (pinfunction "RESET_24") (pintype "input"))
    )
    (net (code "27") (name "/RXD") (class "Default")
      (node (ref "J3") (pin "1") (pintype "passive"))
      (node (ref "U2") (pin "34") (pinfunction "RX0_34") (pintype "passive"))
    )
    (net (code "28") (name "/Role_1") (class "Default")
      (node (ref "R17") (pin "1") (pinfunction "1_1") (pintype "passive"))
      (node (ref "U1") (pin "39") (pinfunction "PB3_39") (pintype "bidirectional"))
    )
    (net (code "29") (name "/Role_2") (class "Default")
      (node (ref "R23") (pin "1") (pinfunction "1_1") (pintype "passive"))
      (node (ref "U1") (pin "40") (pinfunction "PB4_40") (pintype "bidirectional"))
    )
    (net (code "30") (name "/Role_3") (class "Default")
      (node (ref "R27") (pin "1") (pinfunction "1_1") (pintype "passive"))
      (node (ref "U1") (pin "41") (pinfunction "PB5_41") (pintype "bidirectional"))
    )
    (net (code "31") (name "/Role_4") (class "Default")
      (node (ref "R32") (pin "1") (pinfunction "1_1") (pintype "passive"))
      (node (ref "U1") (pin "42") (pinfunction "PB6_42") (pintype "bidirectional"))
    )
    (net (code "32") (name "/SCK") (class "Default")
      (node (ref "J8") (pin "7") (pintype "passive"))
      (node (ref "U1") (pin "15") (pinfunction "PA5_15") (pintype "bidirectional"))
    )
    (net (code "33") (name "/SDI(MOSI)") (class "Default")
      (node (ref "J8") (pin "6") (pintype "passive"))
      (node (ref "U1") (pin "17") (pinfunction "PA7_17") (pintype "bidirectional"))
    )
    (net (code "34") (name "/SWCLK") (class "Default")
      (node (ref "R10") (pin "1") (pinfunction "1_1") (pintype "passive"))
      (node (ref "U1") (pin "37") (pinfunction "PA14_37") (pintype "bidirectional"))
    )
    (net (code "35") (name "/SWDIO") (class "Default")
      (node (ref "R8") (pin "1") (pinfunction "1_1") (pintype "passive"))
      (node (ref "U1") (pin "34") (pinfunction "PA13_34") (pintype "bidirectional"))
    )
    (net (code "36") (name "/TFT_LED") (class "Default")
      (node (ref "J8") (pin "8") (pintype "passive"))
      (node (ref "U15") (pin "D") (pinfunction "D_D") (pintype "passive"))
    )
    (net (code "37") (name "/TXD") (class "Default")
      (node (ref "J3") (pin "2") (pintype "passive"))
      (node (ref "U2") (pin "35") (pinfunction "TX0_35") (pintype "passive"))
    )
    (net (code "38") (name "/UART1_STM_RX") (class "Default")
      (node (ref "U1") (pin "31") (pinfunction "PA10_31") (pintype "bidirectional"))
      (node (ref "U3") (pin "20") (pinfunction "P0.3_20") (pintype "bidirectional"))
    )
    (net (code "39") (name "/UART1_STM_TX") (class "Default")
      (node (ref "U1") (pin "30") (pinfunction "PA9_30") (pintype "bidirectional"))
      (node (ref "U3") (pin "21") (pinfunction "P0.2_21") (pintype "bidirectional"))
    )
    (net (code "40") (name "/UART3_STM_RX") (class "Default")
      (node (ref "U1") (pin "22") (pinfunction "PB11_22") (pintype "bidirectional"))
      (node (ref "U2") (pin "30") (pinfunction "IO18_30") (pintype "passive"))
    )
    (net (code "41") (name "/UART3_STM_TX") (class "Default")
      (node (ref "U1") (pin "21") (pinfunction "PB10_21") (pintype "bidirectional"))
      (node (ref "U2") (pin "31") (pinfunction "IO19_31") (pintype "passive"))
    )
    (net (code "42") (name "GND") (class "Default")
      (node (ref "C1") (pin "1") (pinfunction "1_1") (pintype "passive"))
      (node (ref "C10") (pin "1") (pinfunction "1_1") (pintype "passive"))
      (node (ref "C11") (pin "1") (pinfunction "1_1") (pintype "passive"))
      (node (ref "C12") (pin "1") (pinfunction "1_1") (pintype "passive"))
      (node (ref "C13") (pin "2") (pinfunction "2_2") (pintype "passive"))
      (node (ref "C14") (pin "2") (pinfunction "2_2") (pintype "passive"))
      (node (ref "C15") (pin "1") (pinfunction "1_1") (pintype "passive"))
      (node (ref "C16") (pin "1") (pinfunction "1_1") (pintype "passive"))
      (node (ref "C17") (pin "2") (pinfunction "2_2") (pintype "passive"))
      (node (ref "C18") (pin "2") (pinfunction "2_2") (pintype "passive"))
      (node (ref "C19") (pin "1") (pinfunction "1_1") (pintype "passive"))
      (node (ref "C2") (pin "1") (pinfunction "1_1") (pintype "passive"))
      (node (ref "C20") (pin "2") (pinfunction "2_2") (pintype "passive"))
      (node (ref "C21") (pin "1") (pinfunction "1_1") (pintype "passive"))
      (node (ref "C22") (pin "1") (pinfunction "1_1") (pintype "passive"))
      (node (ref "C23") (pin "2") (pinfunction "2_2") (pintype "passive"))
      (node (ref "C3") (pin "1") (pinfunction "1_1") (pintype "passive"))
      (node (ref "C4") (pin "1") (pinfunction "1_1") (pintype "passive"))
      (node (ref "C5") (pin "1") (pinfunction "1_1") (pintype "passive"))
      (node (ref "C6") (pin "1") (pinfunction "1_1") (pintype "passive"))
      (node (ref "C7") (pin "1") (pinfunction "1_1") (pintype "passive"))
      (node (ref "C8") (pin "1") (pinfunction "1_1") (pintype "passive"))
      (node (ref "C9") (pin "2") (pinfunction "2_2") (pintype "passive"))
      (node (ref "D4") (pin "2") (pinfunction "GND_2") (pintype "passive"))
      (node (ref "D9") (pin "1") (pinfunction "1_1") (pintype "passive"))
      (node (ref "J1") (pin "4") (pintype "passive"))
      (node (ref "J2") (pin "2") (pintype "passive"))
      (node (ref "J3") (pin "3") (pintype "passive"))
      (node (ref "J8") (pin "2") (pintype "passive"))
      (node (ref "Q1") (pin "1") (pinfunction "E_1") (pintype "passive"))
      (node (ref "Q2") (pin "1") (pinfunction "E_1") (pintype "passive"))
      (node (ref "Q3") (pin "1") (pinfunction "E_1") (pintype "passive"))
      (node (ref "Q4") (pin "1") (pinfunction "E_1") (pintype "passive"))
      (node (ref "R2") (pin "2") (pinfunction "2_2") (pintype "passive"))
      (node (ref "R5") (pin "1") (pinfunction "1_1") (pintype "passive"))
      (node (ref "S1") (pin "1") (pinfunction "1_1") (pintype "passive"))
      (node (ref "S2") (pin "2") (pinfunction "2_2") (pintype "passive"))
      (node (ref "S3") (pin "1") (pinfunction "1_1") (pintype "passive"))
      (node (ref "S4") (pin "1") (pinfunction "1_1") (pintype "passive"))
      (node (ref "S5") (pin "2") (pinfunction "2_2") (pintype "passive"))
      (node (ref "S6") (pin "2") (pinfunction "2_2") (pintype "passive"))
      (node (ref "S7") (pin "2") (pinfunction "2_2") (pintype "passive"))
      (node (ref "S8") (pin "2") (pinfunction "2_2") (pintype "passive"))
      (node (ref "S9") (pin "2") (pinfunction "2_2") (pintype "passive"))
      (node (ref "U1") (pin "23") (pinfunction "VSS_1_23") (pintype "power_in"))
      (node (ref "U1") (pin "35") (pinfunction "VSS_2_35") (pintype "power_in"))
      (node (ref "U1") (pin "47") (pinfunction "VSS_3_47") (pintype "power_in"))
      (node (ref "U1") (pin "8") (pinfunction "VSSA_8") (pintype "power_in"))
      (node (ref "U11") (pin "2") (pinfunction "GND_2") (pintype "passive"))
      (node (ref "U12") (pin "3") (pinfunction "GND_3") (pintype "passive"))
      (node (ref "U12") (pin "5") (pinfunction "~{ON}/OFF_5") (pintype "passive"))
      (node (ref "U12") (pin "6") (pinfunction "GND_6") (pintype "passive"))
      (node (ref "U14") (pin "2") (pinfunction "GND_2") (pintype "passive"))
      (node (ref "U16") (pin "1") (pinfunction "GND_1") (pintype "output"))
      (node (ref "U18") (pin "2") (pinfunction "GND_2") (pintype "passive"))
      (node (ref "U19") (pin "4") (pinfunction "GND_4") (pintype "passive"))
      (node (ref "U2") (pin "1") (pinfunction "GND_1") (pintype "passive"))
      (node (ref "U2") (pin "15") (pinfunction "GND_15") (pintype "passive"))
      (node (ref "U2") (pin "38") (pinfunction "GND_38") (pintype "passive"))
      (node (ref "U2") (pin "39") (pinfunction "GND_PAD_39") (pintype "passive"))
      (node (ref "U3") (pin "1") (pinfunction "GND_1") (pintype "power_in"))
      (node (ref "U6") (pin "2") (pinfunction "E_2") (pintype "passive"))
      (node (ref "U7") (pin "4") (pinfunction "4_4") (pintype "passive"))
      (node (ref "U9") (pin "2") (pinfunction "GND_2") (pintype "passive"))
    )
    (net (code "43") (name "Net-(D4-B)") (class "Default")
      (node (ref "D4") (pin "4") (pinfunction "B_4") (pintype "passive"))
      (node (ref "R14") (pin "2") (pinfunction "2_2") (pintype "passive"))
    )
    (net (code "44") (name "Net-(D4-G)") (class "Default")
      (node (ref "D4") (pin "3") (pinfunction "G_3") (pintype "passive"))
      (node (ref "R12") (pin "2") (pinfunction "2_2") (pintype "passive"))
    )
    (net (code "45") (name "Net-(D4-R)") (class "Default")
      (node (ref "D4") (pin "1") (pinfunction "R_1") (pintype "passive"))
      (node (ref "R11") (pin "2") (pinfunction "2_2") (pintype "passive"))
    )
    (net (code "46") (name "Net-(D5-Pad1)") (class "Default")
      (node (ref "D5") (pin "1") (pinfunction "1_1") (pintype "passive"))
      (node (ref "R16") (pin "1") (pinfunction "1_1") (pintype "passive"))
    )
    (net (code "47") (name "Net-(D7-Pad1)") (class "Default")
      (node (ref "D7") (pin "1") (pinfunction "1_1") (pintype "passive"))
      (node (ref "R21") (pin "1") (pinfunction "1_1") (pintype "passive"))
    )
    (net (code "48") (name "Net-(D10-Pad1)") (class "Default")
      (node (ref "D10") (pin "1") (pinfunction "1_1") (pintype "passive"))
      (node (ref "R26") (pin "1") (pinfunction "1_1") (pintype "passive"))
    )
    (net (code "49") (name "Net-(D12-Pad1)") (class "Default")
      (node (ref "D12") (pin "1") (pinfunction "1_1") (pintype "passive"))
      (node (ref "R31") (pin "1") (pinfunction "1_1") (pintype "passive"))
    )
    (net (code "50") (name "Net-(F1-Pad1)") (class "Default")
      (node (ref "F1") (pin "1") (pinfunction "1_1") (pintype "passive"))
      (node (ref "J4") (pin "2") (pinfunction "2_2") (pintype "passive"))
    )
    (net (code "51") (name "Net-(F1-Pad2)") (class "Default")
      (node (ref "F1") (pin "2") (pinfunction "2_2") (pintype "passive"))
      (node (ref "U7") (pin "2") (pinfunction "2_2") (pintype "passive"))
    )
    (net (code "52") (name "Net-(J2-Pad1)") (class "Default")
      (node (ref "J2") (pin "1") (pintype "passive"))
      (node (ref "R8") (pin "2") (pinfunction "2_2") (pintype "passive"))
    )
    (net (code "53") (name "Net-(J2-Pad3)") (class "Default")
      (node (ref "J2") (pin "3") (pintype "passive"))
      (node (ref "R10") (pin "2") (pinfunction "2_2") (pintype "passive"))
    )
    (net (code "54") (name "Net-(J4-Pad1)") (class "Default")
      (node (ref "J4") (pin "1") (pinfunction "1_1") (pintype "passive"))
      (node (ref "U7") (pin "1") (pinfunction "1_1") (pintype "passive"))
    )
    (net (code "55") (name "Net-(J5-Pad1)") (class "Default")
      (node (ref "J5") (pin "1") (pinfunction "1_1") (pintype "passive"))
      (node (ref "U8") (pin "4") (pintype "passive"))
    )
    (net (code "56") (name "Net-(J5-Pad2)") (class "Default")
      (node (ref "J5") (pin "2") (pinfunction "2_2") (pintype "passive"))
      (node (ref "U8") (pin "3") (pintype "passive"))
    )
    (net (code "57") (name "Net-(J5-Pad3)") (class "Default")
      (node (ref "J5") (pin "3") (pinfunction "3_3") (pintype "passive"))
      (node (ref "U8") (pin "5") (pintype "passive"))
    )
    (net (code "58") (name "Net-(J6-Pad1)") (class "Default")
      (node (ref "J6") (pin "1") (pinfunction "1_1") (pintype "passive"))
      (node (ref "U10") (pin "4") (pintype "passive"))
    )
    (net (code "59") (name "Net-(J6-Pad2)") (class "Default")
      (node (ref "J6") (pin "2") (pinfunction "2_2") (pintype "passive"))
      (node (ref "U10") (pin "3") (pintype "passive"))
    )
    (net (code "60") (name "Net-(J6-Pad3)") (class "Default")
      (node (ref "J6") (pin "3") (pinfunction "3_3") (pintype "passive"))
      (node (ref "U10") (pin "5") (pintype "passive"))
    )
    (net (code "61") (name "Net-(J7-Pad1)") (class "Default")
      (node (ref "J7") (pin "1") (pinfunction "1_1") (pintype "passive"))
      (node (ref "U13") (pin "4") (pintype "passive"))
    )
    (net (code "62") (name "Net-(J7-Pad2)") (class "Default")
      (node (ref "J7") (pin "2") (pinfunction "2_2") (pintype "passive"))
      (node (ref "U13") (pin "3") (pintype "passive"))
    )
    (net (code "63") (name "Net-(J7-Pad3)") (class "Default")
      (node (ref "J7") (pin "3") (pinfunction "3_3") (pintype "passive"))
      (node (ref "U13") (pin "5") (pintype "passive"))
    )
    (net (code "64") (name "Net-(J9-Pad1)") (class "Default")
      (node (ref "J9") (pin "1") (pinfunction "1_1") (pintype "passive"))
      (node (ref "U17") (pin "4") (pintype "passive"))
    )
    (net (code "65") (name "Net-(J9-Pad2)") (class "Default")
      (node (ref "J9") (pin "2") (pinfunction "2_2") (pintype "passive"))
      (node (ref "U17") (pin "3") (pintype "passive"))
    )
    (net (code "66") (name "Net-(J9-Pad3)") (class "Default")
      (node (ref "J9") (pin "3") (pinfunction "3_3") (pintype "passive"))
      (node (ref "U17") (pin "5") (pintype "passive"))
    )
    (net (code "67") (name "Net-(Q1-B)") (class "Default")
      (node (ref "Q1") (pin "2") (pinfunction "B_2") (pintype "passive"))
      (node (ref "R18") (pin "2") (pinfunction "2_2") (pintype "passive"))
    )
    (net (code "68") (name "Net-(Q1-C)") (class "Default")
      (node (ref "D5") (pin "2") (pinfunction "2_2") (pintype "passive"))
      (node (ref "D6") (pin "1") (pinfunction "1_1") (pintype "passive"))
      (node (ref "Q1") (pin "3") (pinfunction "C_3") (pintype "passive"))
      (node (ref "U8") (pin "2") (pintype "passive"))
    )
    (net (code "69") (name "Net-(Q2-B)") (class "Default")
      (node (ref "Q2") (pin "2") (pinfunction "B_2") (pintype "passive"))
      (node (ref "R24") (pin "2") (pinfunction "2_2") (pintype "passive"))
    )
    (net (code "70") (name "Net-(Q2-C)") (class "Default")
      (node (ref "D7") (pin "2") (pinfunction "2_2") (pintype "passive"))
      (node (ref "D8") (pin "1") (pinfunction "1_1") (pintype "passive"))
      (node (ref "Q2") (pin "3") (pinfunction "C_3") (pintype "passive"))
      (node (ref "U10") (pin "2") (pintype "passive"))
    )
    (net (code "71") (name "Net-(Q3-B)") (class "Default")
      (node (ref "Q3") (pin "2") (pinfunction "B_2") (pintype "passive"))
      (node (ref "R28") (pin "2") (pinfunction "2_2") (pintype "passive"))
    )
    (net (code "72") (name "Net-(Q3-C)") (class "Default")
      (node (ref "D10") (pin "2") (pinfunction "2_2") (pintype "passive"))
      (node (ref "D11") (pin "1") (pinfunction "1_1") (pintype "passive"))
      (node (ref "Q3") (pin "3") (pinfunction "C_3") (pintype "passive"))
      (node (ref "U13") (pin "2") (pintype "passive"))
    )
    (net (code "73") (name "Net-(Q4-B)") (class "Default")
      (node (ref "Q4") (pin "2") (pinfunction "B_2") (pintype "passive"))
      (node (ref "R33") (pin "2") (pinfunction "2_2") (pintype "passive"))
    )
    (net (code "74") (name "Net-(Q4-C)") (class "Default")
      (node (ref "D12") (pin "2") (pinfunction "2_2") (pintype "passive"))
      (node (ref "D13") (pin "1") (pinfunction "1_1") (pintype "passive"))
      (node (ref "Q4") (pin "3") (pinfunction "C_3") (pintype "passive"))
      (node (ref "U17") (pin "2") (pintype "passive"))
    )
    (net (code "75") (name "Net-(R18-Pad1)") (class "Default")
      (node (ref "R18") (pin "1") (pinfunction "1_1") (pintype "passive"))
      (node (ref "U9") (pin "3") (pinfunction "GND_3") (pintype "passive"))
    )
    (net (code "76") (name "Net-(R24-Pad1)") (class "Default")
      (node (ref "R24") (pin "1") (pinfunction "1_1") (pintype "passive"))
      (node (ref "U11") (pin "3") (pinfunction "GND_3") (pintype "passive"))
    )
    (net (code "77") (name "Net-(R28-Pad1)") (class "Default")
      (node (ref "R28") (pin "1") (pinfunction "1_1") (pintype "passive"))
      (node (ref "U14") (pin "3") (pinfunction "GND_3") (pintype "passive"))
    )
    (net (code "78") (name "Net-(R29-Pad1)") (class "Default")
      (node (ref "R29") (pin "1") (pinfunction "1_1") (pintype "passive"))
      (node (ref "R30") (pin "2") (pinfunction "2_2") (pintype "passive"))
      (node (ref "U15") (pin "G") (pinfunction "G_G") (pintype "passive"))
    )
    (net (code "79") (name "Net-(R33-Pad1)") (class "Default")
      (node (ref "R33") (pin "1") (pinfunction "1_1") (pintype "passive"))
      (node (ref "U18") (pin "3") (pinfunction "GND_3") (pintype "passive"))
    )
    (net (code "80") (name "Net-(U2-IO12)") (class "Default")
      (node (ref "R2") (pin "1") (pinfunction "1_1") (pintype "passive"))
      (node (ref "U2") (pin "14") (pinfunction "IO12_14") (pintype "passive"))
    )
    (net (code "81") (name "Net-(U2-IO15)") (class "Default")
      (node (ref "R6") (pin "1") (pinfunction "1_1") (pintype "passive"))
      (node (ref "U2") (pin "23") (pinfunction "IO15_23") (pintype "passive"))
    )
    (net (code "82") (name "Net-(U5--)") (class "Default")
      (node (ref "U5") (pin "2") (pinfunction "-_2") (pintype "passive"))
      (node (ref "U6") (pin "3") (pinfunction "C_3") (pintype "passive"))
    )
    (net (code "83") (name "Net-(U6-B)") (class "Default")
      (node (ref "R13") (pin "2") (pinfunction "2_2") (pintype "passive"))
      (node (ref "U6") (pin "1") (pinfunction "B_1") (pintype "passive"))
    )
    (net (code "84") (name "Net-(U9-VCC)") (class "Default")
      (node (ref "R17") (pin "2") (pinfunction "2_2") (pintype "passive"))
      (node (ref "U9") (pin "1") (pinfunction "VCC_1") (pintype "passive"))
    )
    (net (code "85") (name "Net-(U11-VCC)") (class "Default")
      (node (ref "R23") (pin "2") (pinfunction "2_2") (pintype "passive"))
      (node (ref "U11") (pin "1") (pinfunction "VCC_1") (pintype "passive"))
    )
    (net (code "86") (name "Net-(U12-VOUT)") (class "Default")
      (node (ref "D9") (pin "2") (pintype "passive"))
      (node (ref "I1") (pin "1") (pinfunction "1_1") (pintype "passive"))
      (node (ref "U12") (pin "2") (pinfunction "VOUT_2") (pintype "passive"))
    )
    (net (code "87") (name "Net-(U14-VCC)") (class "Default")
      (node (ref "R27") (pin "2") (pinfunction "2_2") (pintype "passive"))
      (node (ref "U14") (pin "1") (pinfunction "VCC_1") (pintype "passive"))
    )
    (net (code "88") (name "Net-(U18-VCC)") (class "Default")
      (node (ref "R32") (pin "2") (pinfunction "2_2") (pintype "passive"))
      (node (ref "U18") (pin "1") (pinfunction "VCC_1") (pintype "passive"))
    )
    (net (code "89") (name "unconnected-(U1A-PA6-Pad16)") (class "Default")
      (node (ref "U1") (pin "16") (pinfunction "PA6_16") (pintype "bidirectional"))
    )
    (net (code "90") (name "unconnected-(U1A-PA11-Pad32)") (class "Default")
      (node (ref "U1") (pin "32") (pinfunction "PA11_32") (pintype "bidirectional"))
    )
    (net (code "91") (name "unconnected-(U1A-PA12-Pad33)") (class "Default")
      (node (ref "U1") (pin "33") (pinfunction "PA12_33") (pintype "bidirectional"))
    )
    (net (code "92") (name "unconnected-(U1A-PA15-Pad38)") (class "Default")
      (node (ref "U1") (pin "38") (pinfunction "PA15_38") (pintype "bidirectional"))
    )
    (net (code "93") (name "unconnected-(U1A-PB12-Pad25)") (class "Default")
      (node (ref "U1") (pin "25") (pinfunction "PB12_25") (pintype "bidirectional"))
    )
    (net (code "94") (name "unconnected-(U1A-PB13-Pad26)") (class "Default")
      (node (ref "U1") (pin "26") (pinfunction "PB13_26") (pintype "bidirectional"))
    )
    (net (code "95") (name "unconnected-(U1A-PB14-Pad27)") (class "Default")
      (node (ref "U1") (pin "27") (pinfunction "PB14_27") (pintype "bidirectional"))
    )
    (net (code "96") (name "unconnected-(U1A-PB15-Pad28)") (class "Default")
      (node (ref "U1") (pin "28") (pinfunction "PB15_28") (pintype "bidirectional"))
    )
    (net (code "97") (name "unconnected-(U1A-PC14-OSC32_IN-Pad3)") (class "Default")
      (node (ref "U1") (pin "3") (pinfunction "PC14-OSC32_IN_3") (pintype "bidirectional"))
    )
    (net (code "98") (name "unconnected-(U1A-PC15-OSC32_OUT-Pad4)") (class "Default")
      (node (ref "U1") (pin "4") (pinfunction "PC15-OSC32_OUT_4") (pintype "bidirectional"))
    )
    (net (code "99") (name "unconnected-(U1B-VBAT-Pad1)") (class "Default")
      (node (ref "U1") (pin "1") (pinfunction "VBAT_1") (pintype "power_in"))
    )
    (net (code "100") (name "unconnected-(U2-IO2-Pad24)") (class "Default")
      (node (ref "U2") (pin "24") (pinfunction "IO2_24") (pintype "passive"))
    )
    (net (code "101") (name "unconnected-(U2-IO4-Pad26)") (class "Default")
      (node (ref "U2") (pin "26") (pinfunction "IO4_26") (pintype "passive"))
    )
    (net (code "102") (name "unconnected-(U2-IO5-Pad29)") (class "Default")
      (node (ref "U2") (pin "29") (pinfunction "IO5_29") (pintype "passive"))
    )
    (net (code "103") (name "unconnected-(U2-IO13-Pad16)") (class "Default")
      (node (ref "U2") (pin "16") (pinfunction "IO13_16") (pintype "passive"))
    )
    (net (code "104") (name "unconnected-(U2-IO14-Pad13)") (class "Default")
      (node (ref "U2") (pin "13") (pinfunction "IO14_13") (pintype "passive"))
    )
    (net (code "105") (name "unconnected-(U2-IO16-Pad27)") (class "Default")
      (node (ref "U2") (pin "27") (pinfunction "IO16_27") (pintype "passive"))
    )
    (net (code "106") (name "unconnected-(U2-IO17-Pad28)") (class "Default")
      (node (ref "U2") (pin "28") (pinfunction "IO17_28") (pintype "passive"))
    )
    (net (code "107") (name "unconnected-(U2-IO21-Pad33)") (class "Default")
      (node (ref "U2") (pin "33") (pinfunction "IO21_33") (pintype "passive"))
    )
    (net (code "108") (name "unconnected-(U2-IO22-Pad36)") (class "Default")
      (node (ref "U2") (pin "36") (pinfunction "IO22_36") (pintype "passive"))
    )
    (net (code "109") (name "unconnected-(U2-IO23-Pad37)") (class "Default")
      (node (ref "U2") (pin "37") (pinfunction "IO23_37") (pintype "passive"))
    )
    (net (code "110") (name "unconnected-(U2-IO25-Pad10)") (class "Default")
      (node (ref "U2") (pin "10") (pinfunction "IO25_10") (pintype "passive"))
    )
    (net (code "111") (name "unconnected-(U2-IO26-Pad11)") (class "Default")
      (node (ref "U2") (pin "11") (pinfunction "IO26_11") (pintype "passive"))
    )
    (net (code "112") (name "unconnected-(U2-IO27-Pad12)") (class "Default")
      (node (ref "U2") (pin "12") (pinfunction "IO27_12") (pintype "passive"))
    )
    (net (code "113") (name "unconnected-(U2-IO32-Pad8)") (class "Default")
      (node (ref "U2") (pin "8") (pinfunction "IO32_8") (pintype "passive"))
    )
    (net (code "114") (name "unconnected-(U2-IO33-Pad9)") (class "Default")
      (node (ref "U2") (pin "9") (pinfunction "IO33_9") (pintype "passive"))
    )
    (net (code "115") (name "unconnected-(U2-IO34-Pad6)") (class "Default")
      (node (ref "U2") (pin "6") (pinfunction "IO34_6") (pintype "passive"))
    )
    (net (code "116") (name "unconnected-(U2-IO35-Pad7)") (class "Default")
      (node (ref "U2") (pin "7") (pinfunction "IO35_7") (pintype "passive"))
    )
    (net (code "117") (name "unconnected-(U2-NC-Pad32)") (class "Default")
      (node (ref "U2") (pin "32") (pinfunction "NC_32") (pintype "passive"))
    )
    (net (code "118") (name "unconnected-(U2-SCK{slash}CLK-Pad20)") (class "Default")
      (node (ref "U2") (pin "20") (pinfunction "SCK/CLK_20") (pintype "passive"))
    )
    (net (code "119") (name "unconnected-(U2-SCS{slash}CMD-Pad19)") (class "Default")
      (node (ref "U2") (pin "19") (pinfunction "SCS/CMD_19") (pintype "passive"))
    )
    (net (code "120") (name "unconnected-(U2-SD1{slash}SD1-Pad22)") (class "Default")
      (node (ref "U2") (pin "22") (pinfunction "SD1/SD1_22") (pintype "passive"))
    )
    (net (code "121") (name "unconnected-(U2-SDO{slash}SD0-Pad21)") (class "Default")
      (node (ref "U2") (pin "21") (pinfunction "SDO/SD0_21") (pintype "passive"))
    )
    (net (code "122") (name "unconnected-(U2-SHD{slash}SD3-Pad18)") (class "Default")
      (node (ref "U2") (pin "18") (pinfunction "SHD/SD3_18") (pintype "passive"))
    )
    (net (code "123") (name "unconnected-(U2-SWP{slash}SD2-Pad17)") (class "Default")
      (node (ref "U2") (pin "17") (pinfunction "SWP/SD2_17") (pintype "passive"))
    )
    (net (code "124") (name "unconnected-(U2-VN-Pad5)") (class "Default")
      (node (ref "U2") (pin "5") (pinfunction "VN_5") (pintype "passive"))
    )
    (net (code "125") (name "unconnected-(U2-VP-Pad4)") (class "Default")
      (node (ref "U2") (pin "4") (pinfunction "VP_4") (pintype "passive"))
    )
    (net (code "126") (name "unconnected-(U3-NC-Pad8)") (class "Default")
      (node (ref "U3") (pin "8") (pinfunction "NC_8") (pintype "passive"))
    )
    (net (code "127") (name "unconnected-(U3-NC-Pad9)") (class "Default")
      (node (ref "U3") (pin "9") (pinfunction "NC_9") (pintype "passive"))
    )
    (net (code "128") (name "unconnected-(U3-P0.0-Pad23)") (class "Default")
      (node (ref "U3") (pin "23") (pinfunction "P0.0_23") (pintype "bidirectional"))
    )
    (net (code "129") (name "unconnected-(U3-P0.1-Pad22)") (class "Default")
      (node (ref "U3") (pin "22") (pinfunction "P0.1_22") (pintype "bidirectional"))
    )
    (net (code "130") (name "unconnected-(U3-P0.4-Pad19)") (class "Default")
      (node (ref "U3") (pin "19") (pinfunction "P0.4_19") (pintype "bidirectional"))
    )
    (net (code "131") (name "unconnected-(U3-P0.5-Pad18)") (class "Default")
      (node (ref "U3") (pin "18") (pinfunction "P0.5_18") (pintype "bidirectional"))
    )
    (net (code "132") (name "unconnected-(U3-P0.6-Pad17)") (class "Default")
      (node (ref "U3") (pin "17") (pinfunction "P0.6_17") (pintype "bidirectional"))
    )
    (net (code "133") (name "unconnected-(U3-P0.7-Pad16)") (class "Default")
      (node (ref "U3") (pin "16") (pinfunction "P0.7_16") (pintype "bidirectional"))
    )
    (net (code "134") (name "unconnected-(U3-P1.0-Pad15)") (class "Default")
      (node (ref "U3") (pin "15") (pinfunction "P1.0_15") (pintype "output"))
    )
    (net (code "135") (name "unconnected-(U3-P1.1-Pad14)") (class "Default")
      (node (ref "U3") (pin "14") (pinfunction "P1.1_14") (pintype "output"))
    )
    (net (code "136") (name "unconnected-(U3-P1.2-Pad13)") (class "Default")
      (node (ref "U3") (pin "13") (pinfunction "P1.2_13") (pintype "bidirectional"))
    )
    (net (code "137") (name "unconnected-(U3-P1.3-Pad12)") (class "Default")
      (node (ref "U3") (pin "12") (pinfunction "P1.3_12") (pintype "bidirectional"))
    )
    (net (code "138") (name "unconnected-(U3-P1.4-Pad11)") (class "Default")
      (node (ref "U3") (pin "11") (pinfunction "P1.4_11") (pintype "bidirectional"))
    )
    (net (code "139") (name "unconnected-(U3-P1.5-Pad10)") (class "Default")
      (node (ref "U3") (pin "10") (pinfunction "P1.5_10") (pintype "bidirectional"))
    )
    (net (code "140") (name "unconnected-(U3-P1.6-Pad7)") (class "Default")
      (node (ref "U3") (pin "7") (pinfunction "P1.6_7") (pintype "bidirectional"))
    )
    (net (code "141") (name "unconnected-(U3-P1.7-Pad6)") (class "Default")
      (node (ref "U3") (pin "6") (pinfunction "P1.7_6") (pintype "bidirectional"))
    )
    (net (code "142") (name "unconnected-(U3-P2.0-Pad5)") (class "Default")
      (node (ref "U3") (pin "5") (pinfunction "P2.0_5") (pintype "bidirectional"))
    )
    (net (code "143") (name "unconnected-(U19-NC-Pad3)") (class "Default")
      (node (ref "U19") (pin "3") (pinfunction "NC_3") (pintype "passive+no_connect"))
    )
  )
)
